# clouds_v302_1.net
KiCad netlist of a schematic drawn in Altium Designer
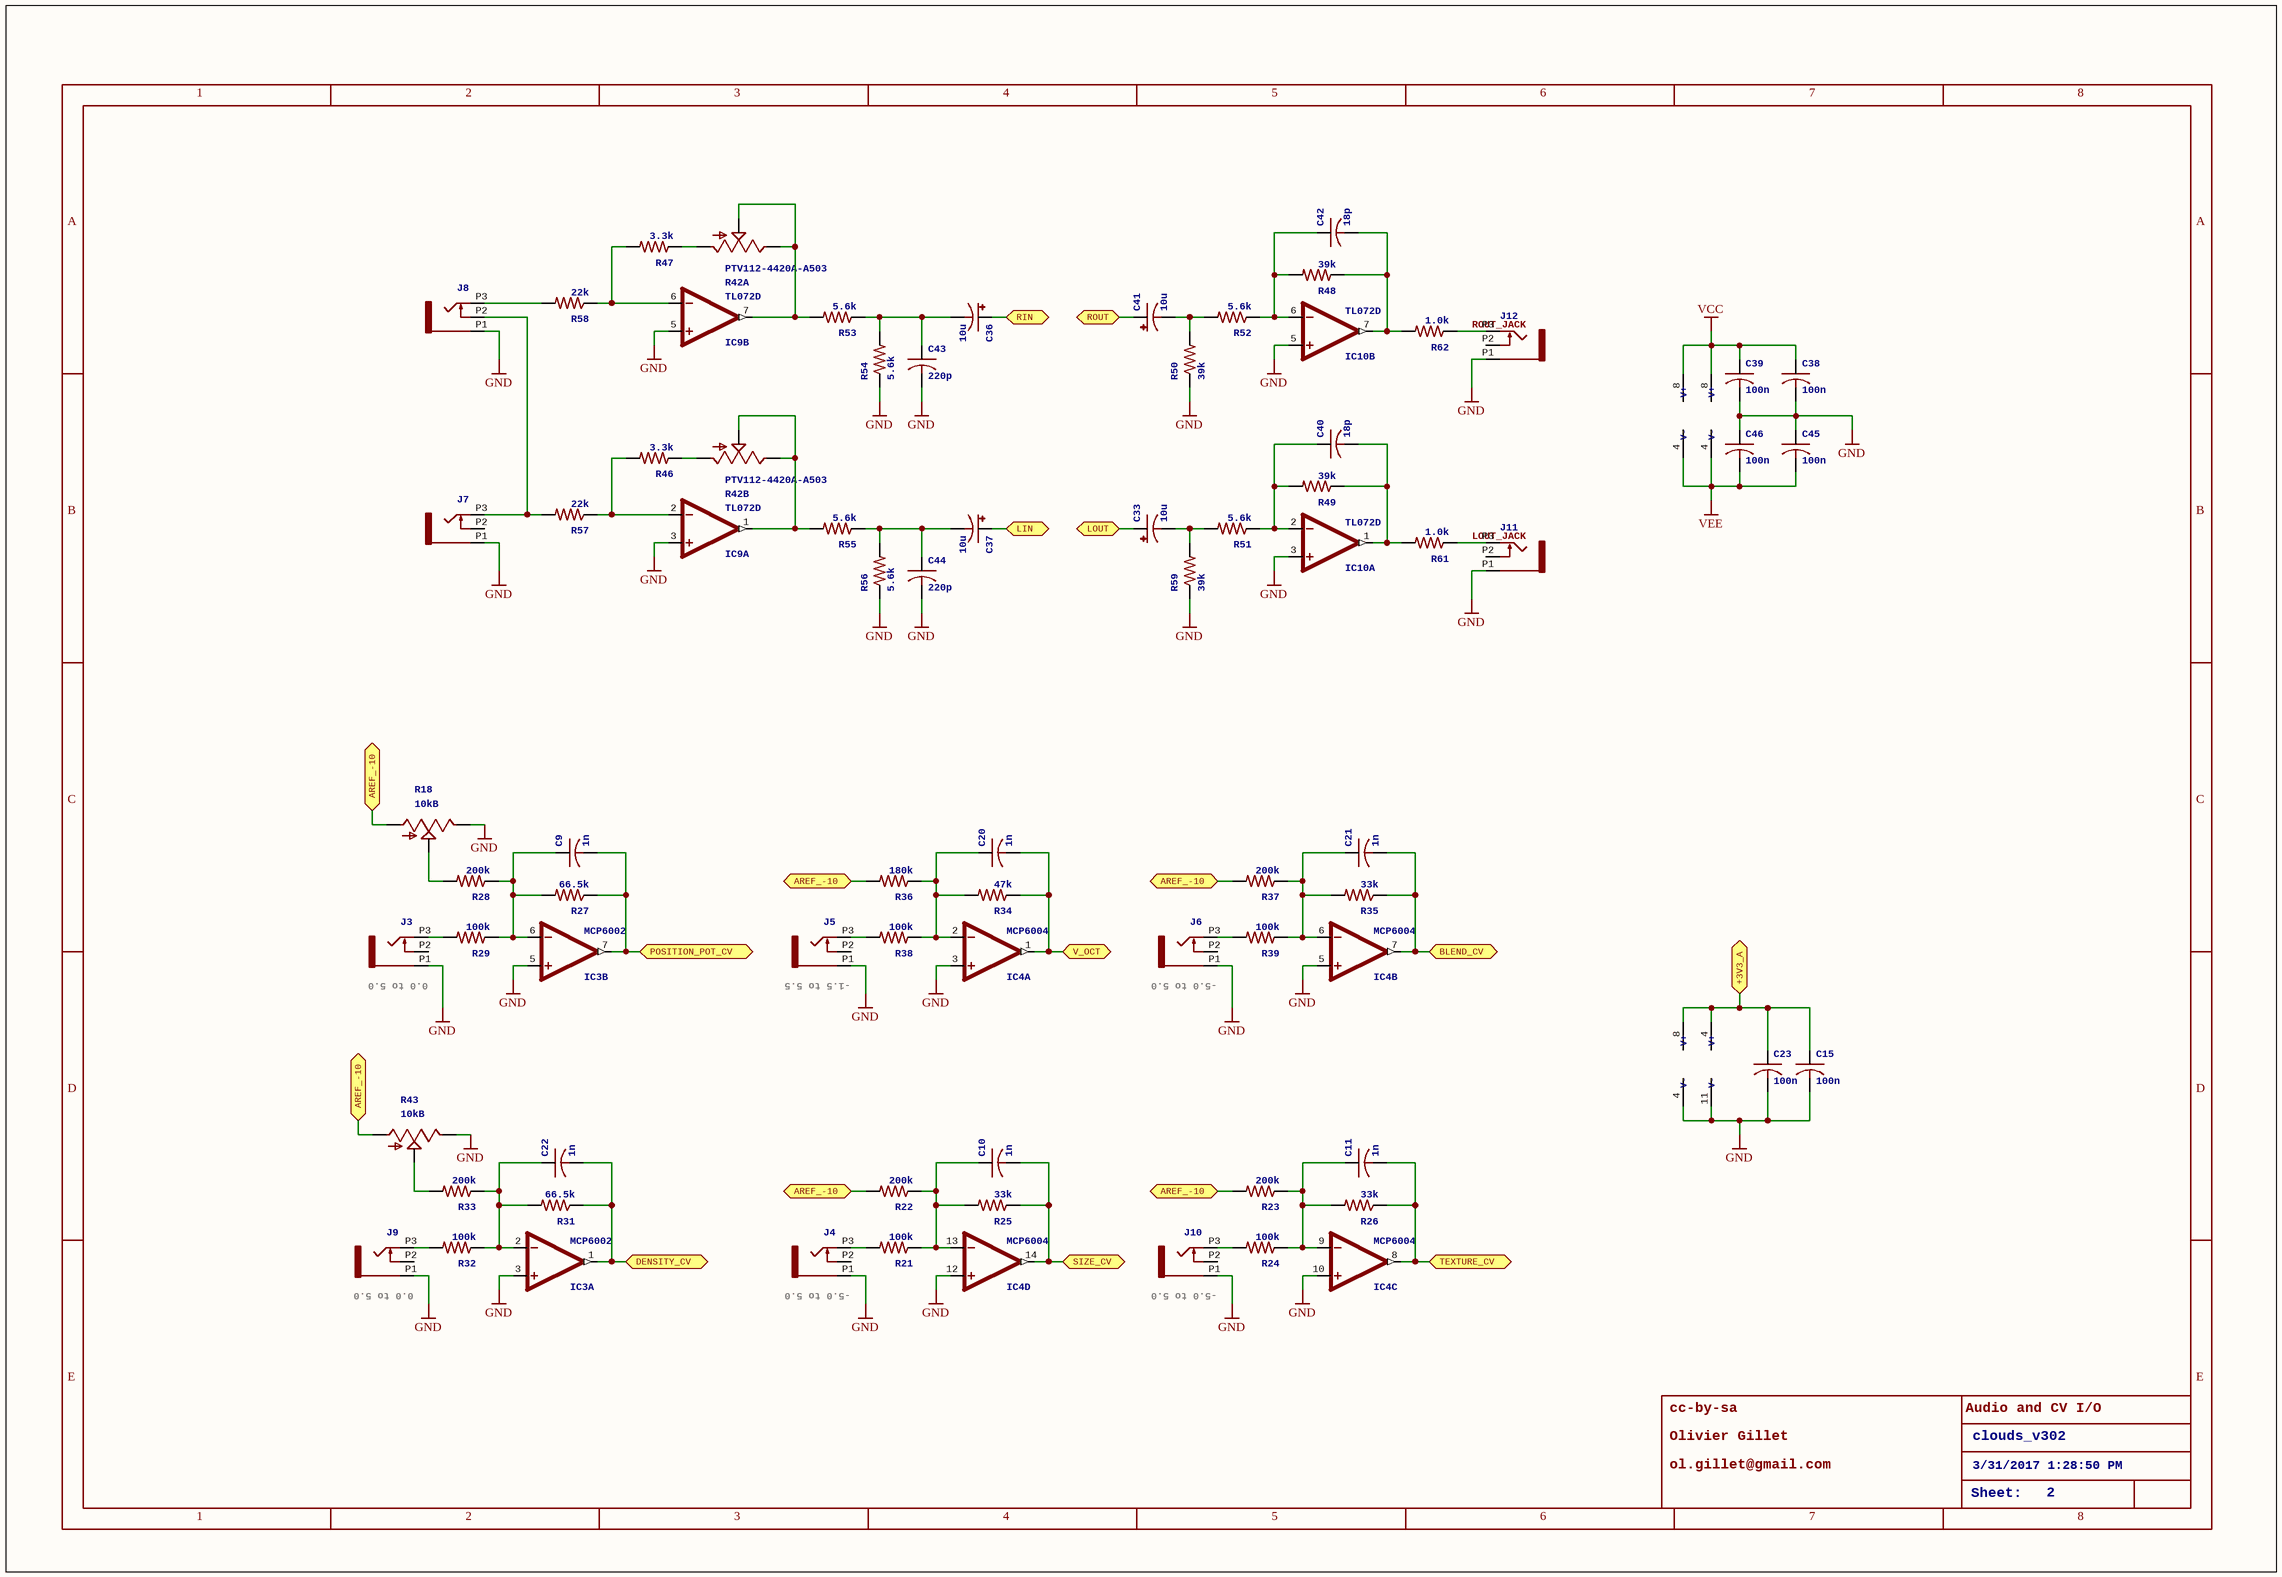
[diagram p0: clouds_v302_1.SchDoc]

(export (version "E")
  (design (tool "Eeschema 10.0.6"))
  (components
    (comp (ref "C9")
      (value "1n")
      (footprint "C0603")
      (description "CAPACITOR, American symbol")
      (libsource (lib "rcl") (part "C-USC0603"))
    )
    (comp (ref "C10")
      (value "1n")
      (footprint "C0603")
      (description "CAPACITOR, American symbol")
      (libsource (lib "rcl") (part "C-USC0603"))
    )
    (comp (ref "C11")
      (value "1n")
      (footprint "C0603")
      (description "CAPACITOR, American symbol")
      (libsource (lib "rcl") (part "C-USC0603"))
    )
    (comp (ref "C15")
      (value "100n")
      (footprint "C0603")
      (description "CAPACITOR, American symbol")
      (libsource (lib "rcl") (part "C-USC0603"))
    )
    (comp (ref "C20")
      (value "1n")
      (footprint "C0603")
      (description "CAPACITOR, American symbol")
      (libsource (lib "rcl") (part "C-USC0603"))
    )
    (comp (ref "C21")
      (value "1n")
      (footprint "C0603")
      (description "CAPACITOR, American symbol")
      (libsource (lib "rcl") (part "C-USC0603"))
    )
    (comp (ref "C22")
      (value "1n")
      (footprint "C0603")
      (description "CAPACITOR, American symbol")
      (libsource (lib "rcl") (part "C-USC0603"))
    )
    (comp (ref "C23")
      (value "100n")
      (footprint "C0603")
      (description "CAPACITOR, American symbol")
      (libsource (lib "rcl") (part "C-USC0603"))
    )
    (comp (ref "C33")
      (value "10u")
      (footprint "PANASONIC_B")
      (description "POLARIZED CAPACITOR, American symbol")
      (libsource (lib "") (part "CPOL-USB_1"))
    )
    (comp (ref "C36")
      (value "10u")
      (footprint "PANASONIC_B")
      (description "POLARIZED CAPACITOR, American symbol")
      (libsource (lib "rcl") (part "CPOL-USB"))
    )
    (comp (ref "C37")
      (value "10u")
      (footprint "PANASONIC_B")
      (description "POLARIZED CAPACITOR, American symbol")
      (libsource (lib "rcl") (part "CPOL-USB"))
    )
    (comp (ref "C38")
      (value "100n")
      (footprint "C0603")
      (description "CAPACITOR, American symbol")
      (libsource (lib "rcl") (part "C-USC0603"))
    )
    (comp (ref "C39")
      (value "100n")
      (footprint "C0603")
      (description "CAPACITOR, American symbol")
      (libsource (lib "rcl") (part "C-USC0603"))
    )
    (comp (ref "C40")
      (value "18p")
      (footprint "C0603")
      (description "CAPACITOR, American symbol")
      (libsource (lib "rcl") (part "C-USC0603"))
    )
    (comp (ref "C41")
      (value "10u")
      (footprint "PANASONIC_B")
      (description "POLARIZED CAPACITOR, American symbol")
      (libsource (lib "") (part "CPOL-USB_1"))
    )
    (comp (ref "C42")
      (value "18p")
      (footprint "C0603")
      (description "CAPACITOR, American symbol")
      (libsource (lib "rcl") (part "C-USC0603"))
    )
    (comp (ref "C43")
      (value "220p")
      (footprint "C0603")
      (description "CAPACITOR, American symbol")
      (libsource (lib "rcl") (part "C-USC0603"))
    )
    (comp (ref "C44")
      (value "220p")
      (footprint "C0603")
      (description "CAPACITOR, American symbol")
      (libsource (lib "rcl") (part "C-USC0603"))
    )
    (comp (ref "C45")
      (value "100n")
      (footprint "C0603")
      (description "CAPACITOR, American symbol")
      (libsource (lib "rcl") (part "C-USC0603"))
    )
    (comp (ref "C46")
      (value "100n")
      (footprint "C0603")
      (description "CAPACITOR, American symbol")
      (libsource (lib "rcl") (part "C-USC0603"))
    )
    (comp (ref "IC3")
      (value "MCP6002")
      (footprint "SO08")
      (description "OP AMP")
      (fields (field (name "V+") "V+") (field (name "V-") "V-"))
      (libsource (lib "gm-ics") (part "TL072D"))
    )
    (comp (ref "IC4")
      (value "MCP6004")
      (footprint "SO14")
      (description "OP AMP")
      (fields (field (name "V+") "V+") (field (name "V-") "V-"))
      (libsource (lib "gm-ics") (part "TL074D"))
    )
    (comp (ref "IC9")
      (value "TL072D")
      (footprint "SO08")
      (description "OP AMP")
      (fields (field (name "V+") "V+") (field (name "V-") "V-"))
      (libsource (lib "og-linear") (part "TL072D"))
    )
    (comp (ref "IC10")
      (value "TL072D")
      (footprint "SO08")
      (description "OP AMP")
      (fields (field (name "V+") "V+") (field (name "V-") "V-"))
      (libsource (lib "og-linear") (part "TL072D"))
    )
    (comp (ref "J3")
      (value "PJ301_THONKICONN6")
      (footprint "WQP_PJ_301M6")
      (libsource (lib "og-pj301") (part "PJ301_THONKICONN6"))
    )
    (comp (ref "J4")
      (value "PJ301_THONKICONN6")
      (footprint "WQP_PJ_301M6")
      (libsource (lib "og-pj301") (part "PJ301_THONKICONN6"))
    )
    (comp (ref "J5")
      (value "PJ301_THONKICONN6")
      (footprint "WQP_PJ_301M6")
      (libsource (lib "og-pj301") (part "PJ301_THONKICONN6"))
    )
    (comp (ref "J6")
      (value "PJ301_THONKICONN6")
      (footprint "WQP_PJ_301M6")
      (libsource (lib "og-pj301") (part "PJ301_THONKICONN6"))
    )
    (comp (ref "J7")
      (value "PJ301_THONKICONN6")
      (footprint "WQP_PJ_301M6")
      (libsource (lib "og-pj301") (part "PJ301_THONKICONN6"))
    )
    (comp (ref "J8")
      (value "PJ301_THONKICONN6")
      (footprint "WQP_PJ_301M6")
      (libsource (lib "og-pj301") (part "PJ301_THONKICONN6"))
    )
    (comp (ref "J9")
      (value "PJ301_THONKICONN6")
      (footprint "WQP_PJ_301M6")
      (libsource (lib "og-pj301") (part "PJ301_THONKICONN6"))
    )
    (comp (ref "J10")
      (value "PJ301_THONKICONN6")
      (footprint "WQP_PJ_301M6")
      (libsource (lib "og-pj301") (part "PJ301_THONKICONN6"))
    )
    (comp (ref "J11")
      (value "PJ301_THONKICONN6")
      (footprint "WQP_PJ_301M6")
      (libsource (lib "") (part "PJ301_THONKICONN6_1"))
    )
    (comp (ref "J12")
      (value "PJ301_THONKICONN6")
      (footprint "WQP_PJ_301M6")
      (libsource (lib "") (part "PJ301_THONKICONN6_1"))
    )
    (comp (ref "R18")
      (value "10kB")
      (footprint "ALPS_POT_VERTICAL_PS")
      (libsource (lib "og-pots") (part "POT_USVERTICAL_PS"))
    )
    (comp (ref "R21")
      (value "100k")
      (footprint "R0603")
      (description "RESISTOR, American symbol")
      (libsource (lib "rcl") (part "R-US_R0603"))
    )
    (comp (ref "R22")
      (value "200k")
      (footprint "R0603")
      (description "RESISTOR, American symbol")
      (libsource (lib "rcl") (part "R-US_R0603"))
    )
    (comp (ref "R23")
      (value "200k")
      (footprint "R0603")
      (description "RESISTOR, American symbol")
      (libsource (lib "rcl") (part "R-US_R0603"))
    )
    (comp (ref "R24")
      (value "100k")
      (footprint "R0603")
      (description "RESISTOR, American symbol")
      (libsource (lib "rcl") (part "R-US_R0603"))
    )
    (comp (ref "R25")
      (value "33k")
      (footprint "R0603")
      (description "RESISTOR, American symbol")
      (libsource (lib "rcl") (part "R-US_R0603"))
    )
    (comp (ref "R26")
      (value "33k")
      (footprint "R0603")
      (description "RESISTOR, American symbol")
      (libsource (lib "rcl") (part "R-US_R0603"))
    )
    (comp (ref "R27")
      (value "66.5k")
      (footprint "R0603")
      (description "RESISTOR, American symbol")
      (libsource (lib "rcl") (part "R-US_R0603"))
    )
    (comp (ref "R28")
      (value "200k")
      (footprint "R0603")
      (description "RESISTOR, American symbol")
      (libsource (lib "rcl") (part "R-US_R0603"))
    )
    (comp (ref "R29")
      (value "100k")
      (footprint "R0603")
      (description "RESISTOR, American symbol")
      (libsource (lib "rcl") (part "R-US_R0603"))
    )
    (comp (ref "R31")
      (value "66.5k")
      (footprint "R0603")
      (description "RESISTOR, American symbol")
      (libsource (lib "rcl") (part "R-US_R0603"))
    )
    (comp (ref "R32")
      (value "100k")
      (footprint "R0603")
      (description "RESISTOR, American symbol")
      (libsource (lib "rcl") (part "R-US_R0603"))
    )
    (comp (ref "R33")
      (value "200k")
      (footprint "R0603")
      (description "RESISTOR, American symbol")
      (libsource (lib "rcl") (part "R-US_R0603"))
    )
    (comp (ref "R34")
      (value "47k")
      (footprint "R0603")
      (description "RESISTOR, American symbol")
      (libsource (lib "rcl") (part "R-US_R0603"))
    )
    (comp (ref "R35")
      (value "33k")
      (footprint "R0603")
      (description "RESISTOR, American symbol")
      (libsource (lib "rcl") (part "R-US_R0603"))
    )
    (comp (ref "R36")
      (value "180k")
      (footprint "R0603")
      (description "RESISTOR, American symbol")
      (libsource (lib "rcl") (part "R-US_R0603"))
    )
    (comp (ref "R37")
      (value "200k")
      (footprint "R0603")
      (description "RESISTOR, American symbol")
      (libsource (lib "rcl") (part "R-US_R0603"))
    )
    (comp (ref "R38")
      (value "100k")
      (footprint "R0603")
      (description "RESISTOR, American symbol")
      (libsource (lib "rcl") (part "R-US_R0603"))
    )
    (comp (ref "R39")
      (value "100k")
      (footprint "R0603")
      (description "RESISTOR, American symbol")
      (libsource (lib "rcl") (part "R-US_R0603"))
    )
    (comp (ref "R42")
      (value "PTV112-4420A-A503")
      (footprint "BOURNS_PTV112")
      (libsource (lib "og-pots") (part "POT_US_DUAL_GANG"))
    )
    (comp (ref "R43")
      (value "10kB")
      (footprint "ALPS_POT_VERTICAL_PS")
      (libsource (lib "og-pots") (part "POT_USVERTICAL_PS"))
    )
    (comp (ref "R46")
      (value "3.3k")
      (footprint "R0603")
      (description "RESISTOR, American symbol")
      (libsource (lib "rcl") (part "R-US_R0603"))
    )
    (comp (ref "R47")
      (value "3.3k")
      (footprint "R0603")
      (description "RESISTOR, American symbol")
      (libsource (lib "rcl") (part "R-US_R0603"))
    )
    (comp (ref "R48")
      (value "39k")
      (footprint "R0603")
      (description "RESISTOR, American symbol")
      (libsource (lib "rcl") (part "R-US_R0603"))
    )
    (comp (ref "R49")
      (value "39k")
      (footprint "R0603")
      (description "RESISTOR, American symbol")
      (libsource (lib "rcl") (part "R-US_R0603"))
    )
    (comp (ref "R50")
      (value "39k")
      (footprint "R0603")
      (description "RESISTOR, American symbol")
      (libsource (lib "rcl") (part "R-US_R0603"))
    )
    (comp (ref "R51")
      (value "5.6k")
      (footprint "R0603")
      (description "RESISTOR, American symbol")
      (libsource (lib "rcl") (part "R-US_R0603"))
    )
    (comp (ref "R52")
      (value "5.6k")
      (footprint "R0603")
      (description "RESISTOR, American symbol")
      (libsource (lib "rcl") (part "R-US_R0603"))
    )
    (comp (ref "R53")
      (value "5.6k")
      (footprint "R0603")
      (description "RESISTOR, American symbol")
      (libsource (lib "rcl") (part "R-US_R0603"))
    )
    (comp (ref "R54")
      (value "5.6k")
      (footprint "R0603")
      (description "RESISTOR, American symbol")
      (libsource (lib "rcl") (part "R-US_R0603"))
    )
    (comp (ref "R55")
      (value "5.6k")
      (footprint "R0603")
      (description "RESISTOR, American symbol")
      (libsource (lib "rcl") (part "R-US_R0603"))
    )
    (comp (ref "R56")
      (value "5.6k")
      (footprint "R0603")
      (description "RESISTOR, American symbol")
      (libsource (lib "rcl") (part "R-US_R0603"))
    )
    (comp (ref "R57")
      (value "22k")
      (footprint "R0603")
      (description "RESISTOR, American symbol")
      (libsource (lib "rcl") (part "R-US_R0603"))
    )
    (comp (ref "R58")
      (value "22k")
      (footprint "R0603")
      (description "RESISTOR, American symbol")
      (libsource (lib "rcl") (part "R-US_R0603"))
    )
    (comp (ref "R59")
      (value "39k")
      (footprint "R0603")
      (description "RESISTOR, American symbol")
      (libsource (lib "rcl") (part "R-US_R0603"))
    )
    (comp (ref "R61")
      (value "1.0k")
      (footprint "R0603")
      (description "RESISTOR, American symbol")
      (libsource (lib "rcl") (part "R-US_R0603"))
    )
    (comp (ref "R62")
      (value "1.0k")
      (footprint "R0603")
      (description "RESISTOR, American symbol")
      (libsource (lib "rcl") (part "R-US_R0603"))
    )
  )
  (nets
    (net (code "1") (name "/+3V3_A") (class "Default")
      (node (ref "C15") (pin "1") (pinfunction "1_1") (pintype "passive"))
      (node (ref "C23") (pin "1") (pinfunction "1_1") (pintype "passive"))
      (node (ref "IC3") (pin "8") (pinfunction "V+_8") (pintype "power_in"))
      (node (ref "IC4") (pin "4") (pinfunction "V+_4") (pintype "power_in"))
    )
    (net (code "2") (name "/AREF_-10") (class "Default")
      (node (ref "R18") (pin "P$3") (pinfunction "A_P$3") (pintype "passive"))
      (node (ref "R22") (pin "2") (pinfunction "2_2") (pintype "passive"))
      (node (ref "R23") (pin "2") (pinfunction "2_2") (pintype "passive"))
      (node (ref "R36") (pin "2") (pinfunction "2_2") (pintype "passive"))
      (node (ref "R37") (pin "2") (pinfunction "2_2") (pintype "passive"))
      (node (ref "R43") (pin "P$3") (pinfunction "A_P$3") (pintype "passive"))
    )
    (net (code "3") (name "/BLEND_CV") (class "Default")
      (node (ref "C21") (pin "2") (pinfunction "2_2") (pintype "passive"))
      (node (ref "IC4") (pin "7") (pinfunction "OUT_7") (pintype "output"))
      (node (ref "R35") (pin "1") (pinfunction "1_1") (pintype "passive"))
    )
    (net (code "4") (name "/DENSITY_CV") (class "Default")
      (node (ref "C22") (pin "2") (pinfunction "2_2") (pintype "passive"))
      (node (ref "IC3") (pin "1") (pinfunction "OUT_1") (pintype "output"))
      (node (ref "R31") (pin "1") (pinfunction "1_1") (pintype "passive"))
    )
    (net (code "5") (name "/LIN") (class "Default")
      (node (ref "C37") (pin "+") (pinfunction "+_+") (pintype "passive"))
    )
    (net (code "6") (name "/LOUT") (class "Default")
      (node (ref "C33") (pin "+") (pinfunction "+_+") (pintype "passive"))
    )
    (net (code "7") (name "/LOUT_JACK") (class "Default")
      (node (ref "J11") (pin "P3") (pinfunction "3_P3") (pintype "passive"))
      (node (ref "R61") (pin "1") (pinfunction "1_1") (pintype "passive"))
    )
    (net (code "8") (name "/POSITION_POT_CV") (class "Default")
      (node (ref "C9") (pin "2") (pinfunction "2_2") (pintype "passive"))
      (node (ref "IC3") (pin "7") (pinfunction "OUT_7") (pintype "output"))
      (node (ref "R27") (pin "1") (pinfunction "1_1") (pintype "passive"))
    )
    (net (code "9") (name "/RIN") (class "Default")
      (node (ref "C36") (pin "+") (pinfunction "+_+") (pintype "passive"))
    )
    (net (code "10") (name "/ROUT") (class "Default")
      (node (ref "C41") (pin "+") (pinfunction "+_+") (pintype "passive"))
    )
    (net (code "11") (name "/ROUT_JACK") (class "Default")
      (node (ref "J12") (pin "P3") (pinfunction "3_P3") (pintype "passive"))
      (node (ref "R62") (pin "1") (pinfunction "1_1") (pintype "passive"))
    )
    (net (code "12") (name "/SIZE_CV") (class "Default")
      (node (ref "C10") (pin "2") (pinfunction "2_2") (pintype "passive"))
      (node (ref "IC4") (pin "14") (pinfunction "OUT_14") (pintype "output"))
      (node (ref "R25") (pin "1") (pinfunction "1_1") (pintype "passive"))
    )
    (net (code "13") (name "/TEXTURE_CV") (class "Default")
      (node (ref "C11") (pin "2") (pinfunction "2_2") (pintype "passive"))
      (node (ref "IC4") (pin "8") (pinfunction "OUT_8") (pintype "output"))
      (node (ref "R26") (pin "1") (pinfunction "1_1") (pintype "passive"))
    )
    (net (code "14") (name "/V_OCT") (class "Default")
      (node (ref "C20") (pin "2") (pinfunction "2_2") (pintype "passive"))
      (node (ref "IC4") (pin "1") (pinfunction "OUT_1") (pintype "output"))
      (node (ref "R34") (pin "1") (pinfunction "1_1") (pintype "passive"))
    )
    (net (code "15") (name "GND") (class "Default")
      (node (ref "C15") (pin "2") (pinfunction "2_2") (pintype "passive"))
      (node (ref "C23") (pin "2") (pinfunction "2_2") (pintype "passive"))
      (node (ref "C38") (pin "2") (pinfunction "2_2") (pintype "passive"))
      (node (ref "C39") (pin "2") (pinfunction "2_2") (pintype "passive"))
      (node (ref "C43") (pin "2") (pinfunction "2_2") (pintype "passive"))
      (node (ref "C44") (pin "2") (pinfunction "2_2") (pintype "passive"))
      (node (ref "C45") (pin "1") (pinfunction "1_1") (pintype "passive"))
      (node (ref "C46") (pin "1") (pinfunction "1_1") (pintype "passive"))
      (node (ref "IC10") (pin "3") (pinfunction "+IN_3") (pintype "passive"))
      (node (ref "IC10") (pin "5") (pinfunction "+IN_5") (pintype "passive"))
      (node (ref "IC3") (pin "3") (pinfunction "+IN_3") (pintype "passive"))
      (node (ref "IC3") (pin "4") (pinfunction "V-_4") (pintype "power_in"))
      (node (ref "IC3") (pin "5") (pinfunction "+IN_5") (pintype "passive"))
      (node (ref "IC4") (pin "10") (pinfunction "+IN_10") (pintype "passive"))
      (node (ref "IC4") (pin "11") (pinfunction "V-_11") (pintype "power_in"))
      (node (ref "IC4") (pin "12") (pinfunction "+IN_12") (pintype "passive"))
      (node (ref "IC4") (pin "3") (pinfunction "+IN_3") (pintype "passive"))
      (node (ref "IC4") (pin "5") (pinfunction "+IN_5") (pintype "passive"))
      (node (ref "IC9") (pin "3") (pinfunction "+IN_3") (pintype "passive"))
      (node (ref "IC9") (pin "5") (pinfunction "+IN_5") (pintype "passive"))
      (node (ref "J10") (pin "P1") (pinfunction "1_P1") (pintype "passive"))
      (node (ref "J11") (pin "P1") (pinfunction "1_P1") (pintype "passive"))
      (node (ref "J12") (pin "P1") (pinfunction "1_P1") (pintype "passive"))
      (node (ref "J3") (pin "P1") (pinfunction "1_P1") (pintype "passive"))
      (node (ref "J4") (pin "P1") (pinfunction "1_P1") (pintype "passive"))
      (node (ref "J5") (pin "P1") (pinfunction "1_P1") (pintype "passive"))
      (node (ref "J6") (pin "P1") (pinfunction "1_P1") (pintype "passive"))
      (node (ref "J7") (pin "P1") (pinfunction "1_P1") (pintype "passive"))
      (node (ref "J8") (pin "P1") (pinfunction "1_P1") (pintype "passive"))
      (node (ref "J9") (pin "P1") (pinfunction "1_P1") (pintype "passive"))
      (node (ref "R18") (pin "P$1") (pinfunction "E_P$1") (pintype "passive"))
      (node (ref "R43") (pin "P$1") (pinfunction "E_P$1") (pintype "passive"))
      (node (ref "R50") (pin "1") (pinfunction "1_1") (pintype "passive"))
      (node (ref "R54") (pin "1") (pinfunction "1_1") (pintype "passive"))
      (node (ref "R56") (pin "1") (pinfunction "1_1") (pintype "passive"))
      (node (ref "R59") (pin "1") (pinfunction "1_1") (pintype "passive"))
    )
    (net (code "16") (name "Net-(C33-Pad-)") (class "Default")
      (node (ref "C33") (pin "-") (pinfunction "-_-") (pintype "passive"))
      (node (ref "R51") (pin "2") (pinfunction "2_2") (pintype "passive"))
      (node (ref "R59") (pin "2") (pinfunction "2_2") (pintype "passive"))
    )
    (net (code "17") (name "Net-(C36-Pad-)") (class "Default")
      (node (ref "C36") (pin "-") (pinfunction "-_-") (pintype "passive"))
      (node (ref "C43") (pin "1") (pinfunction "1_1") (pintype "passive"))
      (node (ref "R53") (pin "1") (pinfunction "1_1") (pintype "passive"))
      (node (ref "R54") (pin "2") (pinfunction "2_2") (pintype "passive"))
    )
    (net (code "18") (name "Net-(C37-Pad-)") (class "Default")
      (node (ref "C37") (pin "-") (pinfunction "-_-") (pintype "passive"))
      (node (ref "C44") (pin "1") (pinfunction "1_1") (pintype "passive"))
      (node (ref "R55") (pin "1") (pinfunction "1_1") (pintype "passive"))
      (node (ref "R56") (pin "2") (pinfunction "2_2") (pintype "passive"))
    )
    (net (code "19") (name "Net-(C41-Pad-)") (class "Default")
      (node (ref "C41") (pin "-") (pinfunction "-_-") (pintype "passive"))
      (node (ref "R50") (pin "2") (pinfunction "2_2") (pintype "passive"))
      (node (ref "R52") (pin "2") (pinfunction "2_2") (pintype "passive"))
    )
    (net (code "20") (name "Net-(IC3A--IN)") (class "Default")
      (node (ref "C22") (pin "1") (pinfunction "1_1") (pintype "passive"))
      (node (ref "IC3") (pin "2") (pinfunction "-IN_2") (pintype "passive"))
      (node (ref "R31") (pin "2") (pinfunction "2_2") (pintype "passive"))
      (node (ref "R32") (pin "1") (pinfunction "1_1") (pintype "passive"))
      (node (ref "R33") (pin "1") (pinfunction "1_1") (pintype "passive"))
    )
    (net (code "21") (name "Net-(IC3B--IN)") (class "Default")
      (node (ref "C9") (pin "1") (pinfunction "1_1") (pintype "passive"))
      (node (ref "IC3") (pin "6") (pinfunction "-IN_6") (pintype "passive"))
      (node (ref "R27") (pin "2") (pinfunction "2_2") (pintype "passive"))
      (node (ref "R28") (pin "1") (pinfunction "1_1") (pintype "passive"))
      (node (ref "R29") (pin "1") (pinfunction "1_1") (pintype "passive"))
    )
    (net (code "22") (name "Net-(IC4A--IN)") (class "Default")
      (node (ref "C20") (pin "1") (pinfunction "1_1") (pintype "passive"))
      (node (ref "IC4") (pin "2") (pinfunction "-IN_2") (pintype "passive"))
      (node (ref "R34") (pin "2") (pinfunction "2_2") (pintype "passive"))
      (node (ref "R36") (pin "1") (pinfunction "1_1") (pintype "passive"))
      (node (ref "R38") (pin "1") (pinfunction "1_1") (pintype "passive"))
    )
    (net (code "23") (name "Net-(IC4B--IN)") (class "Default")
      (node (ref "C21") (pin "1") (pinfunction "1_1") (pintype "passive"))
      (node (ref "IC4") (pin "6") (pinfunction "-IN_6") (pintype "passive"))
      (node (ref "R35") (pin "2") (pinfunction "2_2") (pintype "passive"))
      (node (ref "R37") (pin "1") (pinfunction "1_1") (pintype "passive"))
      (node (ref "R39") (pin "1") (pinfunction "1_1") (pintype "passive"))
    )
    (net (code "24") (name "Net-(IC4C--IN)") (class "Default")
      (node (ref "C11") (pin "1") (pinfunction "1_1") (pintype "passive"))
      (node (ref "IC4") (pin "9") (pinfunction "-IN_9") (pintype "passive"))
      (node (ref "R23") (pin "1") (pinfunction "1_1") (pintype "passive"))
      (node (ref "R24") (pin "1") (pinfunction "1_1") (pintype "passive"))
      (node (ref "R26") (pin "2") (pinfunction "2_2") (pintype "passive"))
    )
    (net (code "25") (name "Net-(IC4D--IN)") (class "Default")
      (node (ref "C10") (pin "1") (pinfunction "1_1") (pintype "passive"))
      (node (ref "IC4") (pin "13") (pinfunction "-IN_13") (pintype "passive"))
      (node (ref "R21") (pin "1") (pinfunction "1_1") (pintype "passive"))
      (node (ref "R22") (pin "1") (pinfunction "1_1") (pintype "passive"))
      (node (ref "R25") (pin "2") (pinfunction "2_2") (pintype "passive"))
    )
    (net (code "26") (name "Net-(IC9A--IN)") (class "Default")
      (node (ref "IC9") (pin "2") (pinfunction "-IN_2") (pintype "passive"))
      (node (ref "R46") (pin "2") (pinfunction "2_2") (pintype "passive"))
      (node (ref "R57") (pin "1") (pinfunction "1_1") (pintype "passive"))
    )
    (net (code "27") (name "Net-(IC9A-OUT)") (class "Default")
      (node (ref "IC9") (pin "1") (pinfunction "OUT_1") (pintype "output"))
      (node (ref "R42") (pin "2") (pinfunction "S_2") (pintype "passive"))
      (node (ref "R42") (pin "3") (pinfunction "E_3") (pintype "passive"))
      (node (ref "R55") (pin "2") (pinfunction "2_2") (pintype "passive"))
    )
    (net (code "28") (name "Net-(IC9B--IN)") (class "Default")
      (node (ref "IC9") (pin "6") (pinfunction "-IN_6") (pintype "passive"))
      (node (ref "R47") (pin "2") (pinfunction "2_2") (pintype "passive"))
      (node (ref "R58") (pin "1") (pinfunction "1_1") (pintype "passive"))
    )
    (net (code "29") (name "Net-(IC9B-OUT)") (class "Default")
      (node (ref "IC9") (pin "7") (pinfunction "OUT_7") (pintype "output"))
      (node (ref "R42") (pin "2P") (pinfunction "S_2P") (pintype "passive"))
      (node (ref "R42") (pin "3P") (pinfunction "E_3P") (pintype "passive"))
      (node (ref "R53") (pin "2") (pinfunction "2_2") (pintype "passive"))
    )
    (net (code "30") (name "Net-(IC10A--IN)") (class "Default")
      (node (ref "C40") (pin "1") (pinfunction "1_1") (pintype "passive"))
      (node (ref "IC10") (pin "2") (pinfunction "-IN_2") (pintype "passive"))
      (node (ref "R49") (pin "2") (pinfunction "2_2") (pintype "passive"))
      (node (ref "R51") (pin "1") (pinfunction "1_1") (pintype "passive"))
    )
    (net (code "31") (name "Net-(IC10A-OUT)") (class "Default")
      (node (ref "C40") (pin "2") (pinfunction "2_2") (pintype "passive"))
      (node (ref "IC10") (pin "1") (pinfunction "OUT_1") (pintype "output"))
      (node (ref "R49") (pin "1") (pinfunction "1_1") (pintype "passive"))
      (node (ref "R61") (pin "2") (pinfunction "2_2") (pintype "passive"))
    )
    (net (code "32") (name "Net-(IC10B--IN)") (class "Default")
      (node (ref "C42") (pin "1") (pinfunction "1_1") (pintype "passive"))
      (node (ref "IC10") (pin "6") (pinfunction "-IN_6") (pintype "passive"))
      (node (ref "R48") (pin "2") (pinfunction "2_2") (pintype "passive"))
      (node (ref "R52") (pin "1") (pinfunction "1_1") (pintype "passive"))
    )
    (net (code "33") (name "Net-(IC10B-OUT)") (class "Default")
      (node (ref "C42") (pin "2") (pinfunction "2_2") (pintype "passive"))
      (node (ref "IC10") (pin "7") (pinfunction "OUT_7") (pintype "output"))
      (node (ref "R48") (pin "1") (pinfunction "1_1") (pintype "passive"))
      (node (ref "R62") (pin "2") (pinfunction "2_2") (pintype "passive"))
    )
    (net (code "34") (name "Net-(J3-3)") (class "Default")
      (node (ref "J3") (pin "P3") (pinfunction "3_P3") (pintype "passive"))
      (node (ref "R29") (pin "2") (pinfunction "2_2") (pintype "passive"))
    )
    (net (code "35") (name "Net-(J4-3)") (class "Default")
      (node (ref "J4") (pin "P3") (pinfunction "3_P3") (pintype "passive"))
      (node (ref "R21") (pin "2") (pinfunction "2_2") (pintype "passive"))
    )
    (net (code "36") (name "Net-(J5-3)") (class "Default")
      (node (ref "J5") (pin "P3") (pinfunction "3_P3") (pintype "passive"))
      (node (ref "R38") (pin "2") (pinfunction "2_2") (pintype "passive"))
    )
    (net (code "37") (name "Net-(J6-3)") (class "Default")
      (node (ref "J6") (pin "P3") (pinfunction "3_P3") (pintype "passive"))
      (node (ref "R39") (pin "2") (pinfunction "2_2") (pintype "passive"))
    )
    (net (code "38") (name "Net-(J7-3)") (class "Default")
      (node (ref "J7") (pin "P3") (pinfunction "3_P3") (pintype "passive"))
      (node (ref "J8") (pin "P2") (pinfunction "2_P2") (pintype "passive"))
      (node (ref "R57") (pin "2") (pinfunction "2_2") (pintype "passive"))
    )
    (net (code "39") (name "Net-(J8-3)") (class "Default")
      (node (ref "J8") (pin "P3") (pinfunction "3_P3") (pintype "passive"))
      (node (ref "R58") (pin "2") (pinfunction "2_2") (pintype "passive"))
    )
    (net (code "40") (name "Net-(J9-3)") (class "Default")
      (node (ref "J9") (pin "P3") (pinfunction "3_P3") (pintype "passive"))
      (node (ref "R32") (pin "2") (pinfunction "2_2") (pintype "passive"))
    )
    (net (code "41") (name "Net-(J10-3)") (class "Default")
      (node (ref "J10") (pin "P3") (pinfunction "3_P3") (pintype "passive"))
      (node (ref "R24") (pin "2") (pinfunction "2_2") (pintype "passive"))
    )
    (net (code "42") (name "Net-(R18-S)") (class "Default")
      (node (ref "R18") (pin "P$2") (pinfunction "S_P$2") (pintype "passive"))
      (node (ref "R28") (pin "2") (pinfunction "2_2") (pintype "passive"))
    )
    (net (code "43") (name "Net-(R42A-A)") (class "Default")
      (node (ref "R42") (pin "1P") (pinfunction "A_1P") (pintype "passive"))
      (node (ref "R47") (pin "1") (pinfunction "1_1") (pintype "passive"))
    )
    (net (code "44") (name "Net-(R42B-A)") (class "Default")
      (node (ref "R42") (pin "1") (pinfunction "A_1") (pintype "passive"))
      (node (ref "R46") (pin "1") (pinfunction "1_1") (pintype "passive"))
    )
    (net (code "45") (name "Net-(R43-S)") (class "Default")
      (node (ref "R33") (pin "2") (pinfunction "2_2") (pintype "passive"))
      (node (ref "R43") (pin "P$2") (pinfunction "S_P$2") (pintype "passive"))
    )
    (net (code "46") (name "VCC") (class "Default")
      (node (ref "C38") (pin "1") (pinfunction "1_1") (pintype "passive"))
      (node (ref "C39") (pin "1") (pinfunction "1_1") (pintype "passive"))
      (node (ref "IC10") (pin "8") (pinfunction "V+_8") (pintype "power_in"))
      (node (ref "IC9") (pin "8") (pinfunction "V+_8") (pintype "power_in"))
    )
    (net (code "47") (name "VEE") (class "Default")
      (node (ref "C45") (pin "2") (pinfunction "2_2") (pintype "passive"))
      (node (ref "C46") (pin "2") (pinfunction "2_2") (pintype "passive"))
      (node (ref "IC10") (pin "4") (pinfunction "V-_4") (pintype "power_in"))
      (node (ref "IC9") (pin "4") (pinfunction "V-_4") (pintype "power_in"))
    )
    (net (code "48") (name "unconnected-(J3-2-PadP2)") (class "Default")
      (node (ref "J3") (pin "P2") (pinfunction "2_P2") (pintype "passive"))
    )
    (net (code "49") (name "unconnected-(J4-2-PadP2)") (class "Default")
      (node (ref "J4") (pin "P2") (pinfunction "2_P2") (pintype "passive"))
    )
    (net (code "50") (name "unconnected-(J5-2-PadP2)") (class "Default")
      (node (ref "J5") (pin "P2") (pinfunction "2_P2") (pintype "passive"))
    )
    (net (code "51") (name "unconnected-(J6-2-PadP2)") (class "Default")
      (node (ref "J6") (pin "P2") (pinfunction "2_P2") (pintype "passive"))
    )
    (net (code "52") (name "unconnected-(J7-2-PadP2)") (class "Default")
      (node (ref "J7") (pin "P2") (pinfunction "2_P2") (pintype "passive"))
    )
    (net (code "53") (name "unconnected-(J9-2-PadP2)") (class "Default")
      (node (ref "J9") (pin "P2") (pinfunction "2_P2") (pintype "passive"))
    )
    (net (code "54") (name "unconnected-(J10-2-PadP2)") (class "Default")
      (node (ref "J10") (pin "P2") (pinfunction "2_P2") (pintype "passive"))
    )
    (net (code "55") (name "unconnected-(J11-2-PadP2)") (class "Default")
      (node (ref "J11") (pin "P2") (pinfunction "2_P2") (pintype "passive"))
    )
    (net (code "56") (name "unconnected-(J12-2-PadP2)") (class "Default")
      (node (ref "J12") (pin "P2") (pinfunction "2_P2") (pintype "passive"))
    )
  )
)
